# POWER.net
KiCad netlist of a schematic drawn in Altium Designer
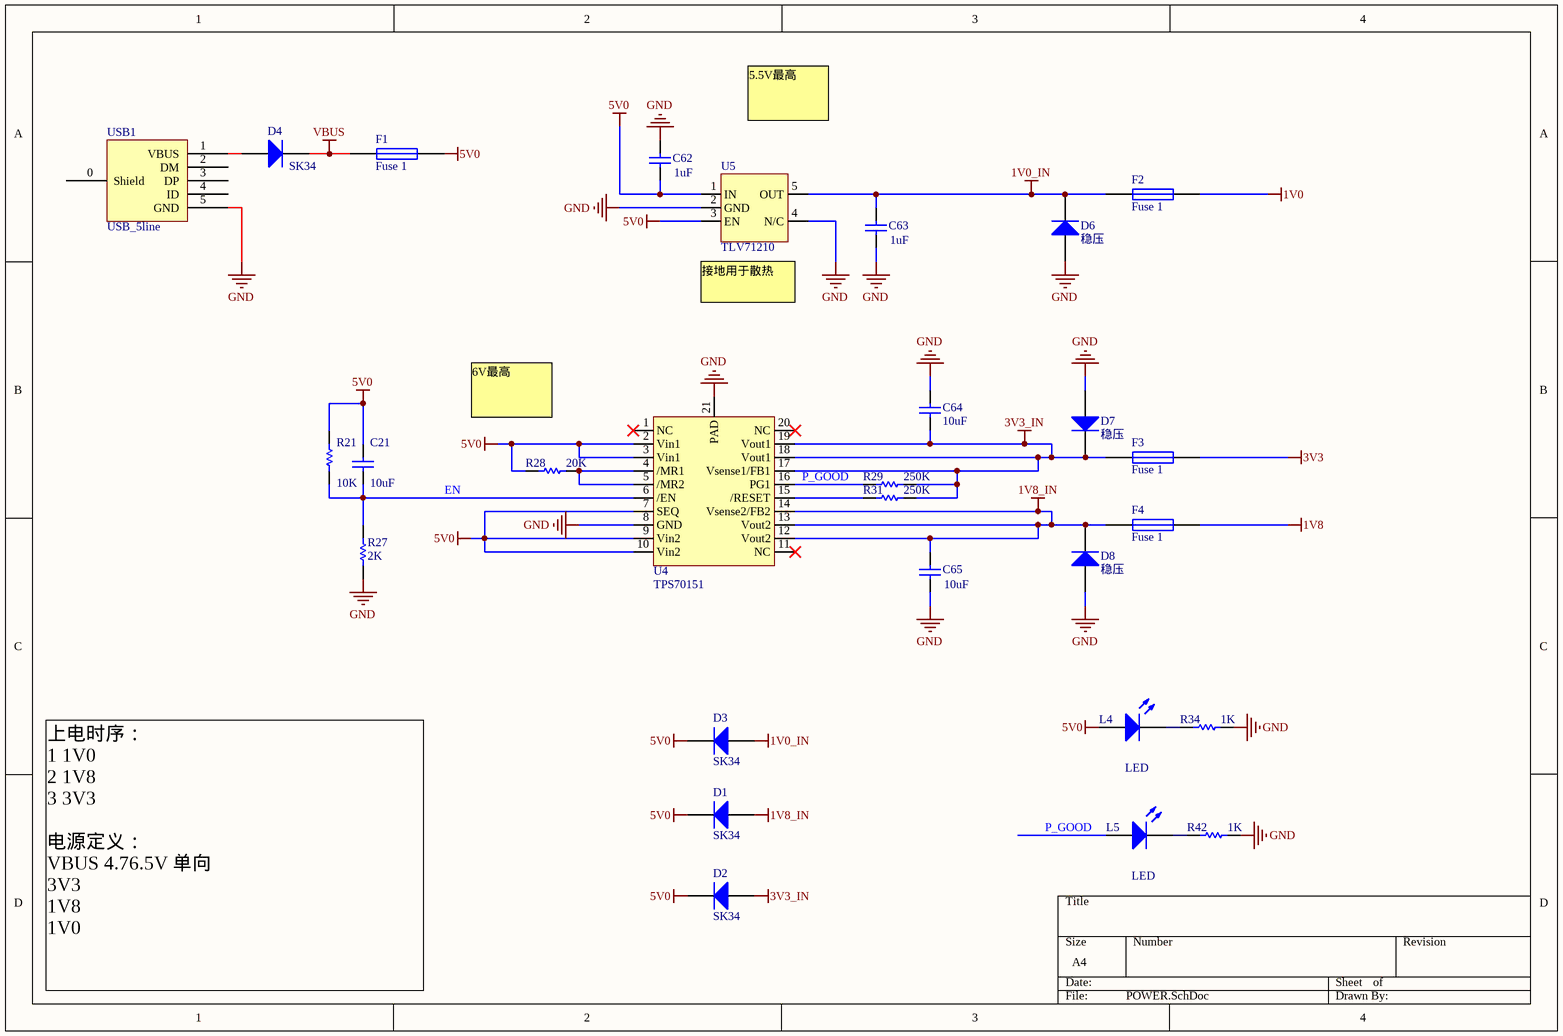
[diagram p0: POWER.SchDoc]

(export (version "E")
  (design (tool "Eeschema 10.0.6"))
  (components
    (comp (ref "C21")
      (value "10uF")
      (footprint "1608[0603]")
      (description "贴片电容")
      (fields (field (name "Comment") "Cap") (field (name "PUBLISHER") "Altium Limited"))
      (libsource (lib "Sparks") (part "Cap"))
    )
    (comp (ref "C62")
      (value "1uF")
      (footprint "1608[0603]")
      (description "贴片电容")
      (fields (field (name "Comment") "Cap") (field (name "PUBLISHER") "Altium Limited"))
      (libsource (lib "Sparks") (part "Cap"))
    )
    (comp (ref "C63")
      (value "1uF")
      (footprint "1608[0603]")
      (description "贴片电容")
      (fields (field (name "Comment") "Cap") (field (name "PUBLISHER") "Altium Limited"))
      (libsource (lib "Sparks") (part "Cap"))
    )
    (comp (ref "C64")
      (value "10uF")
      (footprint "1608[0603]")
      (description "贴片电容")
      (fields (field (name "Comment") "Cap") (field (name "PUBLISHER") "Altium Limited"))
      (libsource (lib "Sparks") (part "Cap"))
    )
    (comp (ref "C65")
      (value "10uF")
      (footprint "1608[0603]")
      (description "贴片电容")
      (fields (field (name "Comment") "Cap") (field (name "PUBLISHER") "Altium Limited"))
      (libsource (lib "Sparks") (part "Cap"))
    )
    (comp (ref "D1")
      (value "SK34")
      (footprint "1206")
      (description "High Conductance Fast Diode")
      (fields (field (name "PUBLISHER") "Altium Limited"))
      (libsource (lib "K60-V4.0") (part "Diode 1N4148"))
    )
    (comp (ref "D2")
      (value "SK34")
      (footprint "1206")
      (description "High Conductance Fast Diode")
      (fields (field (name "PUBLISHER") "Altium Limited"))
      (libsource (lib "K60-V4.0") (part "Diode 1N4148"))
    )
    (comp (ref "D3")
      (value "SK34")
      (footprint "1206")
      (description "High Conductance Fast Diode")
      (fields (field (name "PUBLISHER") "Altium Limited"))
      (libsource (lib "K60-V4.0") (part "Diode 1N4148"))
    )
    (comp (ref "D4")
      (value "SK34")
      (footprint "1206")
      (description "High Conductance Fast Diode")
      (fields (field (name "PUBLISHER") "Altium Limited"))
      (libsource (lib "K60-V4.0") (part "Diode 1N4148"))
    )
    (comp (ref "D6")
      (value "稳压")
      (footprint "1206")
      (description "High Conductance Fast Diode")
      (fields (field (name "PUBLISHER") "Altium Limited"))
      (libsource (lib "K60-V4.0") (part "Diode 1N4148"))
    )
    (comp (ref "D7")
      (value "稳压")
      (footprint "1206")
      (description "High Conductance Fast Diode")
      (fields (field (name "PUBLISHER") "Altium Limited"))
      (libsource (lib "K60-V4.0") (part "Diode 1N4148"))
    )
    (comp (ref "D8")
      (value "稳压")
      (footprint "1206")
      (description "High Conductance Fast Diode")
      (fields (field (name "PUBLISHER") "Altium Limited"))
      (libsource (lib "K60-V4.0") (part "Diode 1N4148"))
    )
    (comp (ref "F1")
      (value "Fuse 1")
      (footprint "1206")
      (description "Fuse")
      (fields (field (name "PUBLISHER") "Altium Limited"))
      (libsource (lib "Miscellaneous Devices") (part "Fuse 1"))
    )
    (comp (ref "F2")
      (value "Fuse 1")
      (footprint "1206")
      (description "Fuse")
      (fields (field (name "PUBLISHER") "Altium Limited"))
      (libsource (lib "Miscellaneous Devices") (part "Fuse 1"))
    )
    (comp (ref "F3")
      (value "Fuse 1")
      (footprint "1206")
      (description "Fuse")
      (fields (field (name "PUBLISHER") "Altium Limited"))
      (libsource (lib "Miscellaneous Devices") (part "Fuse 1"))
    )
    (comp (ref "F4")
      (value "Fuse 1")
      (footprint "1206")
      (description "Fuse")
      (fields (field (name "PUBLISHER") "Altium Limited"))
      (libsource (lib "Miscellaneous Devices") (part "Fuse 1"))
    )
    (comp (ref "L4") (value "LED") (footprint "1608[0603]") (libsource (lib "Sparks") (part "LED")))
    (comp (ref "L5") (value "LED") (footprint "1608[0603]") (libsource (lib "Sparks") (part "LED")))
    (comp (ref "R21")
      (value "10K")
      (footprint "1608[0603]")
      (description "贴片电阻")
      (fields (field (name "Comment") "Res") (field (name "PUBLISHER") "Altium Limited"))
      (libsource (lib "Sparks") (part "Res"))
    )
    (comp (ref "R27")
      (value "2K")
      (footprint "1608[0603]")
      (description "贴片电阻")
      (fields (field (name "Comment") "Res") (field (name "PUBLISHER") "Altium Limited"))
      (libsource (lib "Sparks") (part "Res"))
    )
    (comp (ref "R28")
      (value "20K")
      (footprint "1608[0603]")
      (description "贴片电阻")
      (fields (field (name "Comment") "Res") (field (name "PUBLISHER") "Altium Limited"))
      (libsource (lib "Sparks") (part "Res"))
    )
    (comp (ref "R29")
      (value "250K")
      (footprint "1608[0603]")
      (description "贴片电阻")
      (fields (field (name "Comment") "Res") (field (name "PUBLISHER") "Altium Limited"))
      (libsource (lib "Sparks") (part "Res"))
    )
    (comp (ref "R31")
      (value "250K")
      (footprint "1608[0603]")
      (description "贴片电阻")
      (fields (field (name "Comment") "Res") (field (name "PUBLISHER") "Altium Limited"))
      (libsource (lib "Sparks") (part "Res"))
    )
    (comp (ref "R34")
      (value "1K")
      (footprint "1608[0603]")
      (description "贴片电阻")
      (fields (field (name "Comment") "Res") (field (name "PUBLISHER") "Altium Limited"))
      (libsource (lib "Sparks") (part "Res"))
    )
    (comp (ref "R42")
      (value "1K")
      (footprint "1608[0603]")
      (description "贴片电阻")
      (fields (field (name "Comment") "Res") (field (name "PUBLISHER") "Altium Limited"))
      (libsource (lib "Sparks") (part "Res"))
    )
    (comp (ref "U4") (value "TPS70151") (footprint "TPS701") (libsource (lib "Schlib1") (part "TPS701")))
    (comp (ref "U5") (value "TLV71210") (footprint "TLV712") (libsource (lib "Schlib1") (part "TLV712")))
    (comp (ref "USB1")
      (value "USB_5line")
      (footprint "USB-MICRO-5P-2F")
      (libsource (lib "2号库") (part "USB_5line"))
    )
  )
  (nets
    (net (code "1") (name "/EN") (class "Default")
      (node (ref "C21") (pin "2") (pinfunction "2_2") (pintype "passive"))
      (node (ref "R21") (pin "2") (pinfunction "2_2") (pintype "passive"))
      (node (ref "R27") (pin "1") (pinfunction "1_1") (pintype "passive"))
      (node (ref "U4") (pin "6") (pinfunction "/EN_6") (pintype "passive"))
    )
    (net (code "2") (name "/P_GOOD") (class "Default")
      (node (ref "L5") (pin "1") (pinfunction "A_1") (pintype "passive"))
      (node (ref "R29") (pin "2") (pinfunction "2_2") (pintype "passive"))
      (node (ref "U4") (pin "16") (pinfunction "PG1_16") (pintype "passive"))
    )
    (net (code "3") (name "1V0") (class "Default")
      (node (ref "F2") (pin "1") (pinfunction "1_1") (pintype "passive"))
    )
    (net (code "4") (name "1V0_IN") (class "Default")
      (node (ref "C63") (pin "1") (pinfunction "1_1") (pintype "passive"))
      (node (ref "D3") (pin "1") (pinfunction "A_1") (pintype "passive"))
      (node (ref "D6") (pin "2") (pinfunction "K_2") (pintype "passive"))
      (node (ref "F2") (pin "2") (pinfunction "2_2") (pintype "passive"))
      (node (ref "U5") (pin "5") (pinfunction "OUT_5") (pintype "passive"))
    )
    (net (code "5") (name "1V8") (class "Default")
      (node (ref "F4") (pin "1") (pinfunction "1_1") (pintype "passive"))
    )
    (net (code "6") (name "1V8_IN") (class "Default")
      (node (ref "C65") (pin "1") (pinfunction "1_1") (pintype "passive"))
      (node (ref "D1") (pin "1") (pinfunction "A_1") (pintype "passive"))
      (node (ref "D8") (pin "2") (pinfunction "K_2") (pintype "passive"))
      (node (ref "F4") (pin "2") (pinfunction "2_2") (pintype "passive"))
      (node (ref "U4") (pin "12") (pinfunction "Vout2_12") (pintype "passive"))
      (node (ref "U4") (pin "13") (pinfunction "Vout2_13") (pintype "passive"))
      (node (ref "U4") (pin "14") (pinfunction "Vsense2/FB2_14") (pintype "passive"))
    )
    (net (code "7") (name "3V3") (class "Default")
      (node (ref "F3") (pin "1") (pinfunction "1_1") (pintype "passive"))
    )
    (net (code "8") (name "3V3_IN") (class "Default")
      (node (ref "C64") (pin "1") (pinfunction "1_1") (pintype "passive"))
      (node (ref "D2") (pin "1") (pinfunction "A_1") (pintype "passive"))
      (node (ref "D7") (pin "2") (pinfunction "K_2") (pintype "passive"))
      (node (ref "F3") (pin "2") (pinfunction "2_2") (pintype "passive"))
      (node (ref "R29") (pin "1") (pinfunction "1_1") (pintype "passive"))
      (node (ref "R31") (pin "1") (pinfunction "1_1") (pintype "passive"))
      (node (ref "U4") (pin "17") (pinfunction "Vsense1/FB1_17") (pintype "passive"))
      (node (ref "U4") (pin "18") (pinfunction "Vout1_18") (pintype "passive"))
      (node (ref "U4") (pin "19") (pinfunction "Vout1_19") (pintype "passive"))
    )
    (net (code "9") (name "5V0") (class "Default")
      (node (ref "C21") (pin "1") (pinfunction "1_1") (pintype "passive"))
      (node (ref "C62") (pin "2") (pinfunction "2_2") (pintype "passive"))
      (node (ref "D1") (pin "2") (pinfunction "K_2") (pintype "passive"))
      (node (ref "D2") (pin "2") (pinfunction "K_2") (pintype "passive"))
      (node (ref "D3") (pin "2") (pinfunction "K_2") (pintype "passive"))
      (node (ref "F1") (pin "1") (pinfunction "1_1") (pintype "passive"))
      (node (ref "L4") (pin "1") (pinfunction "A_1") (pintype "passive"))
      (node (ref "R21") (pin "1") (pinfunction "1_1") (pintype "passive"))
      (node (ref "R28") (pin "2") (pinfunction "2_2") (pintype "passive"))
      (node (ref "U4") (pin "10") (pinfunction "Vin2_10") (pintype "passive"))
      (node (ref "U4") (pin "2") (pinfunction "Vin1_2") (pintype "passive"))
      (node (ref "U4") (pin "3") (pinfunction "Vin1_3") (pintype "passive"))
      (node (ref "U4") (pin "7") (pinfunction "SEQ_7") (pintype "passive"))
      (node (ref "U4") (pin "9") (pinfunction "Vin2_9") (pintype "passive"))
      (node (ref "U5") (pin "1") (pinfunction "IN_1") (pintype "passive"))
      (node (ref "U5") (pin "3") (pinfunction "EN_3") (pintype "passive"))
    )
    (net (code "10") (name "GND") (class "Default")
      (node (ref "C62") (pin "1") (pinfunction "1_1") (pintype "passive"))
      (node (ref "C63") (pin "2") (pinfunction "2_2") (pintype "passive"))
      (node (ref "C64") (pin "2") (pinfunction "2_2") (pintype "passive"))
      (node (ref "C65") (pin "2") (pinfunction "2_2") (pintype "passive"))
      (node (ref "D6") (pin "1") (pinfunction "A_1") (pintype "passive"))
      (node (ref "D7") (pin "1") (pinfunction "A_1") (pintype "passive"))
      (node (ref "D8") (pin "1") (pinfunction "A_1") (pintype "passive"))
      (node (ref "R27") (pin "2") (pinfunction "2_2") (pintype "passive"))
      (node (ref "R34") (pin "1") (pinfunction "1_1") (pintype "passive"))
      (node (ref "R42") (pin "1") (pinfunction "1_1") (pintype "passive"))
      (node (ref "U4") (pin "21") (pinfunction "PAD_21") (pintype "passive"))
      (node (ref "U4") (pin "8") (pinfunction "GND_8") (pintype "passive"))
      (node (ref "U5") (pin "2") (pinfunction "GND_2") (pintype "passive"))
      (node (ref "U5") (pin "4") (pinfunction "N/C_4") (pintype "passive"))
      (node (ref "USB1") (pin "5") (pinfunction "GND_5") (pintype "passive"))
    )
    (net (code "11") (name "Net-(D4-A)") (class "Default")
      (node (ref "D4") (pin "1") (pinfunction "A_1") (pintype "passive"))
      (node (ref "USB1") (pin "1") (pinfunction "VBUS_1") (pintype "passive"))
    )
    (net (code "12") (name "Net-(L4-K)") (class "Default")
      (node (ref "L4") (pin "2") (pinfunction "K_2") (pintype "passive"))
      (node (ref "R34") (pin "2") (pinfunction "2_2") (pintype "passive"))
    )
    (net (code "13") (name "Net-(L5-K)") (class "Default")
      (node (ref "L5") (pin "2") (pinfunction "K_2") (pintype "passive"))
      (node (ref "R42") (pin "2") (pinfunction "2_2") (pintype "passive"))
    )
    (net (code "14") (name "Net-(U4-{slash}MR1)") (class "Default")
      (node (ref "R28") (pin "1") (pinfunction "1_1") (pintype "passive"))
      (node (ref "U4") (pin "4") (pinfunction "/MR1_4") (pintype "passive"))
      (node (ref "U4") (pin "5") (pinfunction "/MR2_5") (pintype "passive"))
    )
    (net (code "15") (name "Net-(U4-{slash}RESET)") (class "Default")
      (node (ref "R31") (pin "2") (pinfunction "2_2") (pintype "passive"))
      (node (ref "U4") (pin "15") (pinfunction "/RESET_15") (pintype "passive"))
    )
    (net (code "16") (name "VBUS") (class "Default")
      (node (ref "D4") (pin "2") (pinfunction "K_2") (pintype "passive"))
      (node (ref "F1") (pin "2") (pinfunction "2_2") (pintype "passive"))
    )
    (net (code "17") (name "unconnected-(U4-NC-Pad1)") (class "Default")
      (node (ref "U4") (pin "1") (pinfunction "NC_1") (pintype "passive+no_connect"))
    )
    (net (code "18") (name "unconnected-(U4-NC-Pad11)") (class "Default")
      (node (ref "U4") (pin "11") (pinfunction "NC_11") (pintype "passive+no_connect"))
    )
    (net (code "19") (name "unconnected-(U4-NC-Pad20)") (class "Default")
      (node (ref "U4") (pin "20") (pinfunction "NC_20") (pintype "passive+no_connect"))
    )
    (net (code "20") (name "unconnected-(USB1-DM-Pad2)") (class "Default")
      (node (ref "USB1") (pin "2") (pinfunction "DM_2") (pintype "passive"))
    )
    (net (code "21") (name "unconnected-(USB1-DP-Pad3)") (class "Default")
      (node (ref "USB1") (pin "3") (pinfunction "DP_3") (pintype "passive"))
    )
    (net (code "22") (name "unconnected-(USB1-ID-Pad4)") (class "Default")
      (node (ref "USB1") (pin "4") (pinfunction "ID_4") (pintype "passive"))
    )
    (net (code "23") (name "unconnected-(USB1-Shield-Pad0)") (class "Default")
      (node (ref "USB1") (pin "0") (pinfunction "Shield_0") (pintype "passive"))
    )
  )
)
